# pneumatic_circuit.net
KiCad netlist of a schematic drawn in EAGLE
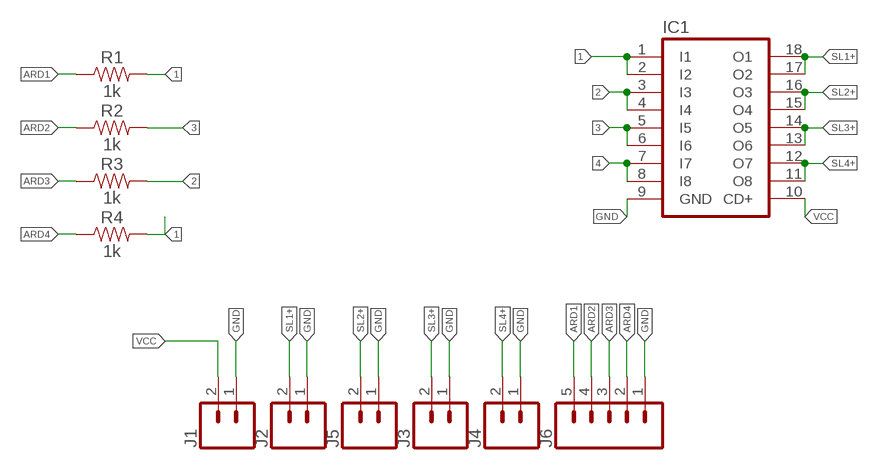
[diagram p0: schematic, sheet 1]

(export (version "E")
  (design (tool "Eeschema 10.0.6"))
  (components
    (comp (ref "IC1")
      (value "ULN2803A")
      (footprint "eagle-import:DIL18")
      (libsource (lib "eagle-import") (part "ULN2803A"))
    )
    (comp (ref "J1")
      (value "CONN_023.5MM")
      (footprint "eagle-import:SCREWTERMINAL-3.5MM-2")
      (libsource (lib "eagle-import") (part "CONN_023.5MM"))
    )
    (comp (ref "J2")
      (value "CONN_023.5MM")
      (footprint "eagle-import:SCREWTERMINAL-3.5MM-2")
      (libsource (lib "eagle-import") (part "CONN_023.5MM"))
    )
    (comp (ref "J3")
      (value "CONN_023.5MM")
      (footprint "eagle-import:SCREWTERMINAL-3.5MM-2")
      (libsource (lib "eagle-import") (part "CONN_023.5MM"))
    )
    (comp (ref "J4")
      (value "CONN_023.5MM")
      (footprint "eagle-import:SCREWTERMINAL-3.5MM-2")
      (libsource (lib "eagle-import") (part "CONN_023.5MM"))
    )
    (comp (ref "J5")
      (value "CONN_023.5MM")
      (footprint "eagle-import:SCREWTERMINAL-3.5MM-2")
      (libsource (lib "eagle-import") (part "CONN_023.5MM"))
    )
    (comp (ref "J6")
      (value "CONN_05")
      (footprint "eagle-import:1X05")
      (libsource (lib "eagle-import") (part "CONN_05"))
    )
    (comp (ref "R1")
      (value "1k")
      (footprint "eagle-import:AXIAL-0.3")
      (libsource (lib "eagle-import") (part "1KOHM-HORIZ-1/4W-5%"))
    )
    (comp (ref "R2")
      (value "1k")
      (footprint "eagle-import:AXIAL-0.3")
      (libsource (lib "eagle-import") (part "1KOHM-HORIZ-1/4W-5%"))
    )
    (comp (ref "R3")
      (value "1k")
      (footprint "eagle-import:AXIAL-0.3")
      (libsource (lib "eagle-import") (part "1KOHM-HORIZ-1/4W-5%"))
    )
    (comp (ref "R4")
      (value "1k")
      (footprint "eagle-import:AXIAL-0.3")
      (libsource (lib "eagle-import") (part "1KOHM-HORIZ-1/4W-5%"))
    )
  )
  (nets
    (net (code "1") (name "1") (class "Default")
      (node (ref "IC1") (pin "1") (pinfunction "I1_1") (pintype "input"))
      (node (ref "IC1") (pin "2") (pinfunction "I2_2") (pintype "input"))
      (node (ref "R4") (pin "P$2") (pinfunction "2_P$2") (pintype "passive"))
    )
    (net (code "2") (name "2") (class "Default")
      (node (ref "IC1") (pin "3") (pinfunction "I3_3") (pintype "input"))
      (node (ref "IC1") (pin "4") (pinfunction "I4_4") (pintype "input"))
      (node (ref "R3") (pin "P$2") (pinfunction "2_P$2") (pintype "passive"))
    )
    (net (code "3") (name "3") (class "Default")
      (node (ref "IC1") (pin "5") (pinfunction "I5_5") (pintype "input"))
      (node (ref "IC1") (pin "6") (pinfunction "I6_6") (pintype "input"))
      (node (ref "R2") (pin "P$2") (pinfunction "2_P$2") (pintype "passive"))
    )
    (net (code "4") (name "4") (class "Default")
      (node (ref "IC1") (pin "7") (pinfunction "I7_7") (pintype "input"))
      (node (ref "IC1") (pin "8") (pinfunction "I8_8") (pintype "input"))
      (node (ref "R1") (pin "P$2") (pinfunction "2_P$2") (pintype "passive"))
    )
    (net (code "5") (name "ARD1") (class "Default")
      (node (ref "J6") (pin "5") (pinfunction "5_5") (pintype "passive"))
      (node (ref "R1") (pin "P$1") (pinfunction "1_P$1") (pintype "passive"))
    )
    (net (code "6") (name "ARD2") (class "Default")
      (node (ref "J6") (pin "4") (pinfunction "4_4") (pintype "passive"))
      (node (ref "R2") (pin "P$1") (pinfunction "1_P$1") (pintype "passive"))
    )
    (net (code "7") (name "ARD3") (class "Default")
      (node (ref "J6") (pin "3") (pinfunction "3_3") (pintype "passive"))
      (node (ref "R3") (pin "P$1") (pinfunction "1_P$1") (pintype "passive"))
    )
    (net (code "8") (name "ARD4") (class "Default")
      (node (ref "J6") (pin "2") (pinfunction "2_2") (pintype "passive"))
      (node (ref "R4") (pin "P$1") (pinfunction "1_P$1") (pintype "passive"))
    )
    (net (code "9") (name "GND") (class "Default")
      (node (ref "IC1") (pin "9") (pinfunction "GND_9") (pintype "power_in"))
      (node (ref "J1") (pin "1") (pinfunction "1_1") (pintype "passive"))
      (node (ref "J2") (pin "1") (pinfunction "1_1") (pintype "passive"))
      (node (ref "J3") (pin "1") (pinfunction "1_1") (pintype "passive"))
      (node (ref "J4") (pin "1") (pinfunction "1_1") (pintype "passive"))
      (node (ref "J5") (pin "1") (pinfunction "1_1") (pintype "passive"))
      (node (ref "J6") (pin "1") (pinfunction "1_1") (pintype "passive"))
    )
    (net (code "10") (name "SL1+") (class "Default")
      (node (ref "IC1") (pin "17") (pinfunction "O2_17") (pintype "open_collector"))
      (node (ref "IC1") (pin "18") (pinfunction "O1_18") (pintype "open_collector"))
      (node (ref "J2") (pin "2") (pinfunction "2_2") (pintype "passive"))
    )
    (net (code "11") (name "SL2+") (class "Default")
      (node (ref "IC1") (pin "15") (pinfunction "O4_15") (pintype "open_collector"))
      (node (ref "IC1") (pin "16") (pinfunction "O3_16") (pintype "open_collector"))
      (node (ref "J5") (pin "2") (pinfunction "2_2") (pintype "passive"))
    )
    (net (code "12") (name "SL3+") (class "Default")
      (node (ref "IC1") (pin "13") (pinfunction "O6_13") (pintype "open_collector"))
      (node (ref "IC1") (pin "14") (pinfunction "O5_14") (pintype "open_collector"))
      (node (ref "J3") (pin "2") (pinfunction "2_2") (pintype "passive"))
    )
    (net (code "13") (name "SL4+") (class "Default")
      (node (ref "IC1") (pin "11") (pinfunction "O8_11") (pintype "open_collector"))
      (node (ref "IC1") (pin "12") (pinfunction "O7_12") (pintype "open_collector"))
      (node (ref "J4") (pin "2") (pinfunction "2_2") (pintype "passive"))
    )
    (net (code "14") (name "VCC") (class "Default")
      (node (ref "IC1") (pin "10") (pinfunction "CD+_10") (pintype "passive"))
      (node (ref "J1") (pin "2") (pinfunction "2_2") (pintype "passive"))
    )
  )
)
